# RSP2NRF.net
KiCad netlist of a schematic drawn in EAGLE
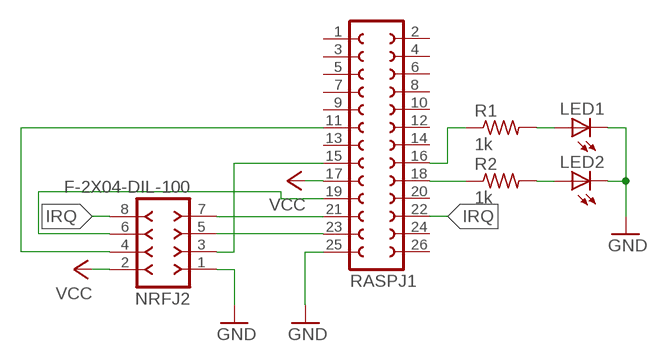
[diagram p0: schematic, sheet 1]

(export (version "E")
  (design (tool "Eeschema 10.0.6"))
  (components
    (comp (ref "LED1")
      (value "LEDCHIPLED_0805")
      (footprint "eagle-import:CHIPLED_0805")
      (fields (field (name "MPN") "OVS-0808"))
      (libsource (lib "eagle-import") (part "LEDCHIPLED_0805"))
    )
    (comp (ref "LED2")
      (value "LEDCHIPLED_0805")
      (footprint "eagle-import:CHIPLED_0805")
      (fields (field (name "MPN") "OVS-0808"))
      (libsource (lib "eagle-import") (part "LEDCHIPLED_0805"))
    )
    (comp (ref "NRFJ2")
      (value "F-2X04-DIL-100")
      (footprint "eagle-import:DIL-100-2X04")
      (libsource (lib "eagle-import") (part "F-2X04-DIL-100"))
    )
    (comp (ref "R1")
      (value "1k")
      (footprint "eagle-import:R0805")
      (fields (field (name "MF") "VISHAY/DALE") (field (name "MPN") "CRCW20101K00FKEF"))
      (libsource (lib "eagle-import") (part "R-US_R0805"))
    )
    (comp (ref "R2")
      (value "1k")
      (footprint "eagle-import:R0805")
      (fields (field (name "MF") "VISHAY/DALE") (field (name "MPN") "CRCW20101K00FKEF"))
      (libsource (lib "eagle-import") (part "R-US_R0805"))
    )
    (comp (ref "RASPJ1")
      (value "FE13-2")
      (footprint "eagle-import:FE13-2")
      (libsource (lib "eagle-import") (part "FE13-2"))
    )
  )
  (nets
    (net (code "1") (name "GND") (class "Default")
      (node (ref "LED1") (pin "C") (pinfunction "C_C") (pintype "passive"))
      (node (ref "LED2") (pin "C") (pinfunction "C_C") (pintype "passive"))
      (node (ref "NRFJ2") (pin "1") (pinfunction "1_1") (pintype "passive"))
      (node (ref "RASPJ1") (pin "25") (pinfunction "25_25") (pintype "passive"))
    )
    (net (code "2") (name "IRQ") (class "Default")
      (node (ref "NRFJ2") (pin "8") (pinfunction "8_8") (pintype "passive"))
      (node (ref "RASPJ1") (pin "22") (pinfunction "22_22") (pintype "passive"))
    )
    (net (code "3") (name "Net-(LED1-PadA)") (class "Default")
      (node (ref "LED1") (pin "A") (pinfunction "A_A") (pintype "passive"))
      (node (ref "R1") (pin "2") (pinfunction "2_2") (pintype "passive"))
    )
    (net (code "4") (name "Net-(LED2-PadA)") (class "Default")
      (node (ref "LED2") (pin "A") (pinfunction "A_A") (pintype "passive"))
      (node (ref "R2") (pin "2") (pinfunction "2_2") (pintype "passive"))
    )
    (net (code "5") (name "Net-(NRFJ2-Pad3)") (class "Default")
      (node (ref "NRFJ2") (pin "3") (pinfunction "3_3") (pintype "passive"))
      (node (ref "RASPJ1") (pin "15") (pinfunction "15_15") (pintype "passive"))
    )
    (net (code "6") (name "Net-(NRFJ2-Pad4)") (class "Default")
      (node (ref "NRFJ2") (pin "4") (pinfunction "4_4") (pintype "passive"))
      (node (ref "RASPJ1") (pin "11") (pinfunction "11_11") (pintype "passive"))
    )
    (net (code "7") (name "Net-(NRFJ2-Pad5)") (class "Default")
      (node (ref "NRFJ2") (pin "5") (pinfunction "5_5") (pintype "passive"))
      (node (ref "RASPJ1") (pin "23") (pinfunction "23_23") (pintype "passive"))
    )
    (net (code "8") (name "Net-(NRFJ2-Pad6)") (class "Default")
      (node (ref "NRFJ2") (pin "6") (pinfunction "6_6") (pintype "passive"))
      (node (ref "RASPJ1") (pin "19") (pinfunction "19_19") (pintype "passive"))
    )
    (net (code "9") (name "Net-(NRFJ2-Pad7)") (class "Default")
      (node (ref "NRFJ2") (pin "7") (pinfunction "7_7") (pintype "passive"))
      (node (ref "RASPJ1") (pin "21") (pinfunction "21_21") (pintype "passive"))
    )
    (net (code "10") (name "Net-(R1-Pad1)") (class "Default")
      (node (ref "R1") (pin "1") (pinfunction "1_1") (pintype "passive"))
      (node (ref "RASPJ1") (pin "16") (pinfunction "16_16") (pintype "passive"))
    )
    (net (code "11") (name "Net-(R2-Pad1)") (class "Default")
      (node (ref "R2") (pin "1") (pinfunction "1_1") (pintype "passive"))
      (node (ref "RASPJ1") (pin "18") (pinfunction "18_18") (pintype "passive"))
    )
    (net (code "12") (name "VCC") (class "Default")
      (node (ref "NRFJ2") (pin "2") (pinfunction "2_2") (pintype "passive"))
      (node (ref "RASPJ1") (pin "17") (pinfunction "17_17") (pintype "passive"))
    )
    (net (code "13") (name "unconnected-(RASPJ1-Pad1)") (class "Default")
      (node (ref "RASPJ1") (pin "1") (pinfunction "1_1") (pintype "passive"))
    )
    (net (code "14") (name "unconnected-(RASPJ1-Pad2)") (class "Default")
      (node (ref "RASPJ1") (pin "2") (pinfunction "2_2") (pintype "passive"))
    )
    (net (code "15") (name "unconnected-(RASPJ1-Pad3)") (class "Default")
      (node (ref "RASPJ1") (pin "3") (pinfunction "3_3") (pintype "passive"))
    )
    (net (code "16") (name "unconnected-(RASPJ1-Pad4)") (class "Default")
      (node (ref "RASPJ1") (pin "4") (pinfunction "4_4") (pintype "passive"))
    )
    (net (code "17") (name "unconnected-(RASPJ1-Pad5)") (class "Default")
      (node (ref "RASPJ1") (pin "5") (pinfunction "5_5") (pintype "passive"))
    )
    (net (code "18") (name "unconnected-(RASPJ1-Pad6)") (class "Default")
      (node (ref "RASPJ1") (pin "6") (pinfunction "6_6") (pintype "passive"))
    )
    (net (code "19") (name "unconnected-(RASPJ1-Pad7)") (class "Default")
      (node (ref "RASPJ1") (pin "7") (pinfunction "7_7") (pintype "passive"))
    )
    (net (code "20") (name "unconnected-(RASPJ1-Pad8)") (class "Default")
      (node (ref "RASPJ1") (pin "8") (pinfunction "8_8") (pintype "passive"))
    )
    (net (code "21") (name "unconnected-(RASPJ1-Pad9)") (class "Default")
      (node (ref "RASPJ1") (pin "9") (pinfunction "9_9") (pintype "passive"))
    )
    (net (code "22") (name "unconnected-(RASPJ1-Pad10)") (class "Default")
      (node (ref "RASPJ1") (pin "10") (pinfunction "10_10") (pintype "passive"))
    )
    (net (code "23") (name "unconnected-(RASPJ1-Pad12)") (class "Default")
      (node (ref "RASPJ1") (pin "12") (pinfunction "12_12") (pintype "passive"))
    )
    (net (code "24") (name "unconnected-(RASPJ1-Pad13)") (class "Default")
      (node (ref "RASPJ1") (pin "13") (pinfunction "13_13") (pintype "passive"))
    )
    (net (code "25") (name "unconnected-(RASPJ1-Pad14)") (class "Default")
      (node (ref "RASPJ1") (pin "14") (pinfunction "14_14") (pintype "passive"))
    )
    (net (code "26") (name "unconnected-(RASPJ1-Pad20)") (class "Default")
      (node (ref "RASPJ1") (pin "20") (pinfunction "20_20") (pintype "passive"))
    )
    (net (code "27") (name "unconnected-(RASPJ1-Pad24)") (class "Default")
      (node (ref "RASPJ1") (pin "24") (pinfunction "24_24") (pintype "passive"))
    )
    (net (code "28") (name "unconnected-(RASPJ1-Pad26)") (class "Default")
      (node (ref "RASPJ1") (pin "26") (pinfunction "26_26") (pintype "passive"))
    )
  )
)
